# Connectors.net
KiCad netlist of a schematic drawn in Altium Designer
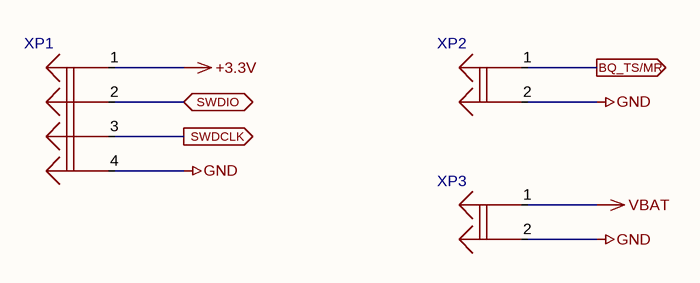
[diagram p0: Connectors.SchDoc]

(export (version "E")
  (design (tool "Eeschema 10.0.6"))
  (components
    (comp (ref "XP1")
      (value "MOLEX 781710004")
      (footprint "MOLEX 781710004")
      (description "1.20mm Pitch, Pico-EZmate PCB Header, Single Row, Gold Plating, Friction Lock, 4 Circuits")
      (libsource (lib "Connectors") (part "MOLEX 781710004"))
    )
    (comp (ref "XP2")
      (value "MOLEX 781710002")
      (footprint "MOLEX 781710002")
      (description "1.20mm Pitch, Pico-EZmate PCB Header, Single Row, Gold Plating, Friction Lock, 2 Circuits")
      (libsource (lib "Connectors") (part "MOLEX 781710002"))
    )
    (comp (ref "XP3")
      (value "MOLEX 781710002")
      (footprint "MOLEX 781710002")
      (description "1.20mm Pitch, Pico-EZmate PCB Header, Single Row, Gold Plating, Friction Lock, 2 Circuits")
      (libsource (lib "Connectors") (part "MOLEX 781710002"))
    )
  )
  (nets
    (net (code "1") (name "+3.3V") (class "Default") (node (ref "XP1") (pin "1") (pintype "passive")))
    (net (code "2") (name "/BQ_TS{slash}MR") (class "Default")
      (node (ref "XP2") (pin "1") (pintype "passive"))
    )
    (net (code "3") (name "/SWDCLK") (class "Default") (node (ref "XP1") (pin "3") (pintype "passive")))
    (net (code "4") (name "/SWDIO") (class "Default") (node (ref "XP1") (pin "2") (pintype "passive")))
    (net (code "5") (name "GND") (class "Default")
      (node (ref "XP1") (pin "4") (pintype "passive"))
      (node (ref "XP2") (pin "2") (pintype "passive"))
      (node (ref "XP3") (pin "2") (pintype "passive"))
    )
    (net (code "6") (name "VBAT") (class "Default") (node (ref "XP3") (pin "1") (pintype "passive")))
  )
)
